# On_Off_Switches.net
KiCad netlist of a schematic drawn in Altium Designer
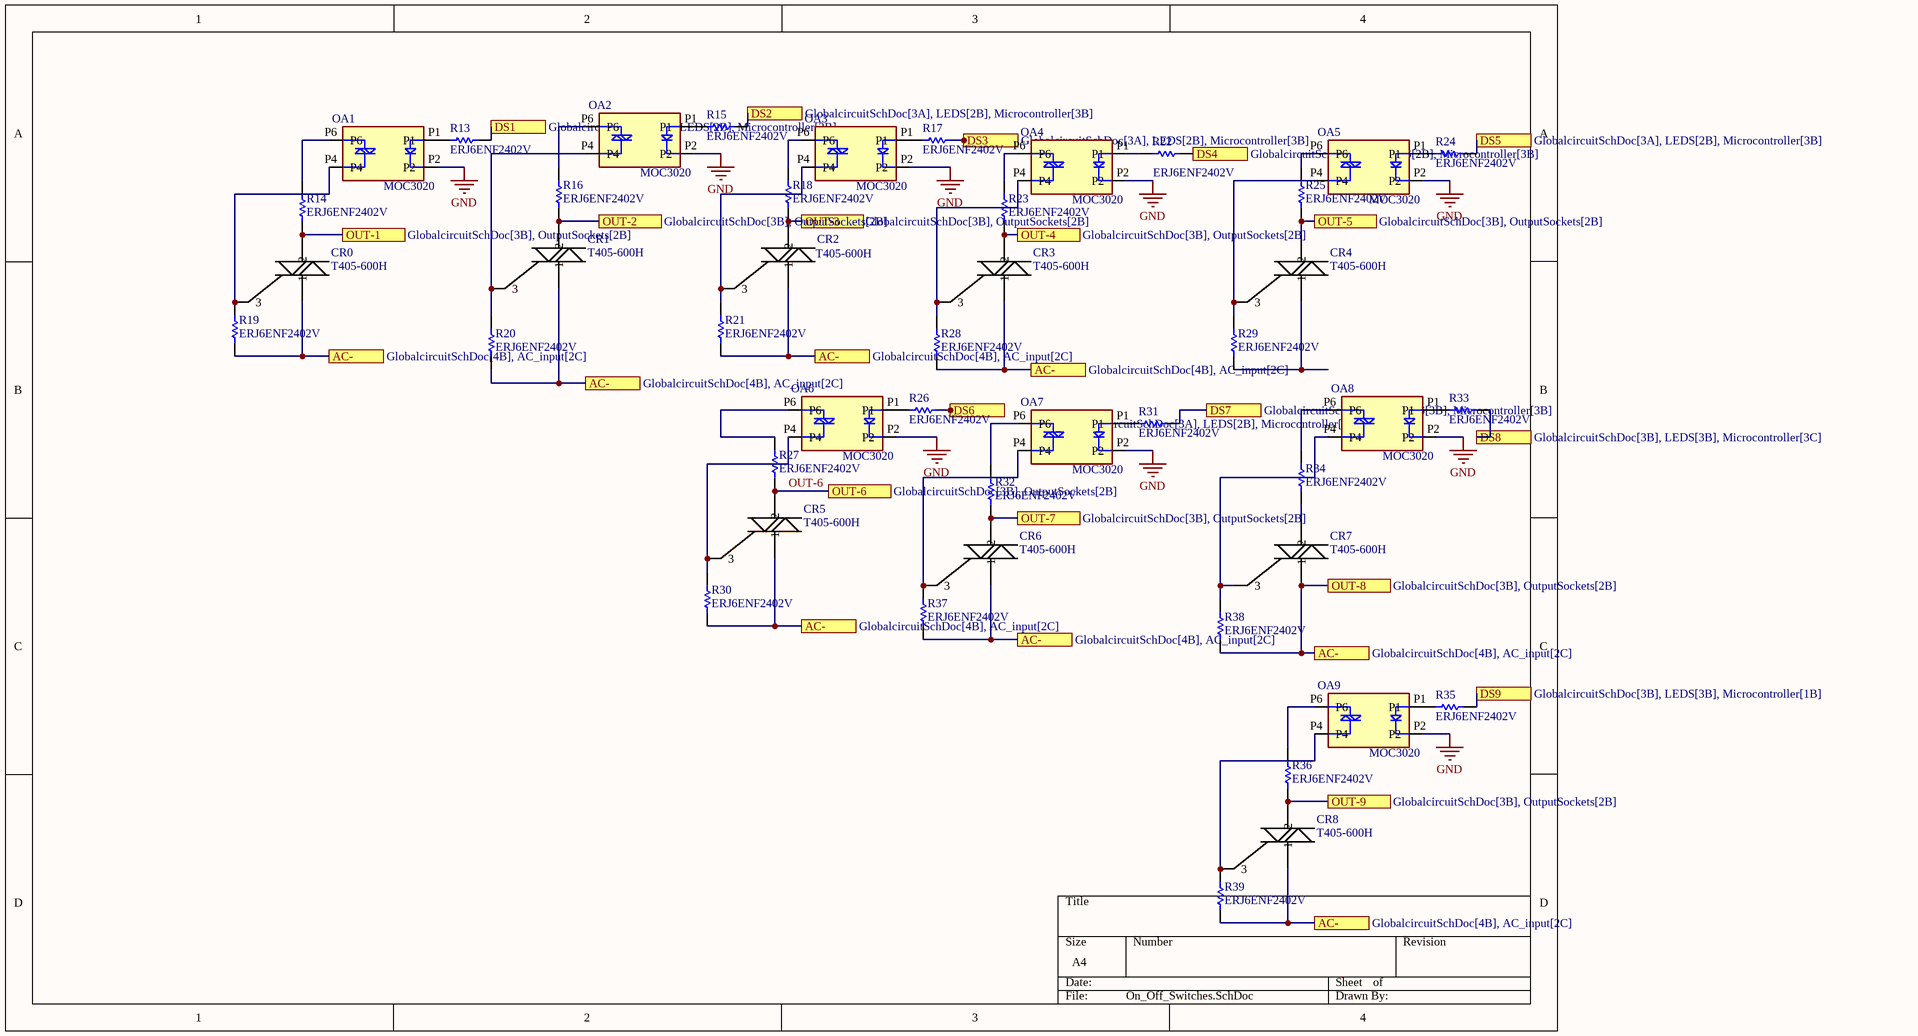
[diagram p0: On_Off_Switches.SchDoc]

(export (version "E")
  (design (tool "Eeschema 10.0.6"))
  (components
    (comp (ref "CR0")
      (value "T405-600H")
      (footprint "IPAK_STM")
      (description "No Description Available")
      (libsource (lib "T405-600H") (part "T405-600H"))
    )
    (comp (ref "CR1")
      (value "T405-600H")
      (footprint "IPAK_STM")
      (description "No Description Available")
      (libsource (lib "T405-600H") (part "T405-600H"))
    )
    (comp (ref "CR2")
      (value "T405-600H")
      (footprint "IPAK_STM")
      (description "No Description Available")
      (libsource (lib "T405-600H") (part "T405-600H"))
    )
    (comp (ref "CR3")
      (value "T405-600H")
      (footprint "IPAK_STM")
      (description "No Description Available")
      (libsource (lib "T405-600H") (part "T405-600H"))
    )
    (comp (ref "CR4")
      (value "T405-600H")
      (footprint "IPAK_STM")
      (description "No Description Available")
      (libsource (lib "T405-600H") (part "T405-600H"))
    )
    (comp (ref "CR5")
      (value "T405-600H")
      (footprint "IPAK_STM")
      (description "No Description Available")
      (libsource (lib "T405-600H") (part "T405-600H"))
    )
    (comp (ref "CR6")
      (value "T405-600H")
      (footprint "IPAK_STM")
      (description "No Description Available")
      (libsource (lib "T405-600H") (part "T405-600H"))
    )
    (comp (ref "CR7")
      (value "T405-600H")
      (footprint "IPAK_STM")
      (description "No Description Available")
      (libsource (lib "T405-600H") (part "T405-600H"))
    )
    (comp (ref "CR8")
      (value "T405-600H")
      (footprint "IPAK_STM")
      (description "No Description Available")
      (libsource (lib "T405-600H") (part "T405-600H"))
    )
    (comp (ref "OA1")
      (value "MOC3020S")
      (footprint "MOC3020S")
      (description "Optoisolator Triac Output 5000Vrms 1 Channel 6-SMD")
      (fields (field (name "MF") "Lite-On Inc."))
      (libsource (lib "MOC3020S") (part "MOC3020S"))
    )
    (comp (ref "OA2")
      (value "MOC3020S")
      (footprint "MOC3020S")
      (description "Optoisolator Triac Output 5000Vrms 1 Channel 6-SMD")
      (fields (field (name "MF") "Lite-On Inc."))
      (libsource (lib "MOC3020S") (part "MOC3020S"))
    )
    (comp (ref "OA3")
      (value "MOC3020S")
      (footprint "MOC3020S")
      (description "Optoisolator Triac Output 5000Vrms 1 Channel 6-SMD")
      (fields (field (name "MF") "Lite-On Inc."))
      (libsource (lib "MOC3020S") (part "MOC3020S"))
    )
    (comp (ref "OA4")
      (value "MOC3020S")
      (footprint "MOC3020S")
      (description "Optoisolator Triac Output 5000Vrms 1 Channel 6-SMD")
      (fields (field (name "MF") "Lite-On Inc."))
      (libsource (lib "MOC3020S") (part "MOC3020S"))
    )
    (comp (ref "OA5")
      (value "MOC3020S")
      (footprint "MOC3020S")
      (description "Optoisolator Triac Output 5000Vrms 1 Channel 6-SMD")
      (fields (field (name "MF") "Lite-On Inc."))
      (libsource (lib "MOC3020S") (part "MOC3020S"))
    )
    (comp (ref "OA6")
      (value "MOC3020S")
      (footprint "MOC3020S")
      (description "Optoisolator Triac Output 5000Vrms 1 Channel 6-SMD")
      (fields (field (name "MF") "Lite-On Inc."))
      (libsource (lib "MOC3020S") (part "MOC3020S"))
    )
    (comp (ref "OA7")
      (value "MOC3020S")
      (footprint "MOC3020S")
      (description "Optoisolator Triac Output 5000Vrms 1 Channel 6-SMD")
      (fields (field (name "MF") "Lite-On Inc."))
      (libsource (lib "MOC3020S") (part "MOC3020S"))
    )
    (comp (ref "OA8")
      (value "MOC3020S")
      (footprint "MOC3020S")
      (description "Optoisolator Triac Output 5000Vrms 1 Channel 6-SMD")
      (fields (field (name "MF") "Lite-On Inc."))
      (libsource (lib "MOC3020S") (part "MOC3020S"))
    )
    (comp (ref "OA9")
      (value "MOC3020S")
      (footprint "MOC3020S")
      (description "Optoisolator Triac Output 5000Vrms 1 Channel 6-SMD")
      (fields (field (name "MF") "Lite-On Inc."))
      (libsource (lib "MOC3020S") (part "MOC3020S"))
    )
    (comp (ref "R13")
      (value "ERJ6ENF2402V")
      (footprint "RESC2013X70X40ML20T20")
      (fields (field (name "MANUFACTURER") "Panasonic"))
      (libsource (lib "Altium Content Vault") (part "RES"))
    )
    (comp (ref "R14")
      (value "ERJ6ENF2402V")
      (footprint "RESC2013X70X40ML20T20")
      (fields (field (name "MANUFACTURER") "Panasonic"))
      (libsource (lib "Altium Content Vault") (part "RES"))
    )
    (comp (ref "R15")
      (value "ERJ6ENF2402V")
      (footprint "RESC2013X70X40ML20T20")
      (fields (field (name "MANUFACTURER") "Panasonic"))
      (libsource (lib "Altium Content Vault") (part "RES"))
    )
    (comp (ref "R16")
      (value "ERJ6ENF2402V")
      (footprint "RESC2013X70X40ML20T20")
      (fields (field (name "MANUFACTURER") "Panasonic"))
      (libsource (lib "Altium Content Vault") (part "RES"))
    )
    (comp (ref "R17")
      (value "ERJ6ENF2402V")
      (footprint "RESC2013X70X40ML20T20")
      (fields (field (name "MANUFACTURER") "Panasonic"))
      (libsource (lib "Altium Content Vault") (part "RES"))
    )
    (comp (ref "R18")
      (value "ERJ6ENF2402V")
      (footprint "RESC2013X70X40ML20T20")
      (fields (field (name "MANUFACTURER") "Panasonic"))
      (libsource (lib "Altium Content Vault") (part "RES"))
    )
    (comp (ref "R19")
      (value "ERJ6ENF2402V")
      (footprint "RESC2013X70X40ML20T20")
      (fields (field (name "MANUFACTURER") "Panasonic"))
      (libsource (lib "Altium Content Vault") (part "RES"))
    )
    (comp (ref "R20")
      (value "ERJ6ENF2402V")
      (footprint "RESC2013X70X40ML20T20")
      (fields (field (name "MANUFACTURER") "Panasonic"))
      (libsource (lib "Altium Content Vault") (part "RES"))
    )
    (comp (ref "R21")
      (value "ERJ6ENF2402V")
      (footprint "RESC2013X70X40ML20T20")
      (fields (field (name "MANUFACTURER") "Panasonic"))
      (libsource (lib "Altium Content Vault") (part "RES"))
    )
    (comp (ref "R22")
      (value "ERJ6ENF2402V")
      (footprint "RESC2013X70X40ML20T20")
      (fields (field (name "MANUFACTURER") "Panasonic"))
      (libsource (lib "Altium Content Vault") (part "RES"))
    )
    (comp (ref "R23")
      (value "ERJ6ENF2402V")
      (footprint "RESC2013X70X40ML20T20")
      (fields (field (name "MANUFACTURER") "Panasonic"))
      (libsource (lib "Altium Content Vault") (part "RES"))
    )
    (comp (ref "R24")
      (value "ERJ6ENF2402V")
      (footprint "RESC2013X70X40ML20T20")
      (fields (field (name "MANUFACTURER") "Panasonic"))
      (libsource (lib "Altium Content Vault") (part "RES"))
    )
    (comp (ref "R25")
      (value "ERJ6ENF2402V")
      (footprint "RESC2013X70X40ML20T20")
      (fields (field (name "MANUFACTURER") "Panasonic"))
      (libsource (lib "Altium Content Vault") (part "RES"))
    )
    (comp (ref "R26")
      (value "ERJ6ENF2402V")
      (footprint "RESC2013X70X40ML20T20")
      (fields (field (name "MANUFACTURER") "Panasonic"))
      (libsource (lib "Altium Content Vault") (part "RES"))
    )
    (comp (ref "R27")
      (value "ERJ6ENF2402V")
      (footprint "RESC2013X70X40ML20T20")
      (fields (field (name "MANUFACTURER") "Panasonic"))
      (libsource (lib "Altium Content Vault") (part "RES"))
    )
    (comp (ref "R28")
      (value "ERJ6ENF2402V")
      (footprint "RESC2013X70X40ML20T20")
      (fields (field (name "MANUFACTURER") "Panasonic"))
      (libsource (lib "Altium Content Vault") (part "RES"))
    )
    (comp (ref "R29")
      (value "ERJ6ENF2402V")
      (footprint "RESC2013X70X40ML20T20")
      (fields (field (name "MANUFACTURER") "Panasonic"))
      (libsource (lib "Altium Content Vault") (part "RES"))
    )
    (comp (ref "R30")
      (value "ERJ6ENF2402V")
      (footprint "RESC2013X70X40ML20T20")
      (fields (field (name "MANUFACTURER") "Panasonic"))
      (libsource (lib "Altium Content Vault") (part "RES"))
    )
    (comp (ref "R31")
      (value "ERJ6ENF2402V")
      (footprint "RESC2013X70X40ML20T20")
      (fields (field (name "MANUFACTURER") "Panasonic"))
      (libsource (lib "Altium Content Vault") (part "RES"))
    )
    (comp (ref "R32")
      (value "ERJ6ENF2402V")
      (footprint "RESC2013X70X40ML20T20")
      (fields (field (name "MANUFACTURER") "Panasonic"))
      (libsource (lib "Altium Content Vault") (part "RES"))
    )
    (comp (ref "R33")
      (value "ERJ6ENF2402V")
      (footprint "RESC2013X70X40ML20T20")
      (fields (field (name "MANUFACTURER") "Panasonic"))
      (libsource (lib "Altium Content Vault") (part "RES"))
    )
    (comp (ref "R34")
      (value "ERJ6ENF2402V")
      (footprint "RESC2013X70X40ML20T20")
      (fields (field (name "MANUFACTURER") "Panasonic"))
      (libsource (lib "Altium Content Vault") (part "RES"))
    )
    (comp (ref "R35")
      (value "ERJ6ENF2402V")
      (footprint "RESC2013X70X40ML20T20")
      (fields (field (name "MANUFACTURER") "Panasonic"))
      (libsource (lib "Altium Content Vault") (part "RES"))
    )
    (comp (ref "R36")
      (value "ERJ6ENF2402V")
      (footprint "RESC2013X70X40ML20T20")
      (fields (field (name "MANUFACTURER") "Panasonic"))
      (libsource (lib "Altium Content Vault") (part "RES"))
    )
    (comp (ref "R37")
      (value "ERJ6ENF2402V")
      (footprint "RESC2013X70X40ML20T20")
      (fields (field (name "MANUFACTURER") "Panasonic"))
      (libsource (lib "Altium Content Vault") (part "RES"))
    )
    (comp (ref "R38")
      (value "ERJ6ENF2402V")
      (footprint "RESC2013X70X40ML20T20")
      (fields (field (name "MANUFACTURER") "Panasonic"))
      (libsource (lib "Altium Content Vault") (part "RES"))
    )
    (comp (ref "R39")
      (value "ERJ6ENF2402V")
      (footprint "RESC2013X70X40ML20T20")
      (fields (field (name "MANUFACTURER") "Panasonic"))
      (libsource (lib "Altium Content Vault") (part "RES"))
    )
  )
  (nets
    (net (code "1") (name "/AC-") (class "Default")
      (node (ref "CR0") (pin "1") (pinfunction "1_1") (pintype "passive"))
      (node (ref "CR1") (pin "1") (pinfunction "1_1") (pintype "passive"))
      (node (ref "CR2") (pin "1") (pinfunction "1_1") (pintype "passive"))
      (node (ref "CR3") (pin "1") (pinfunction "1_1") (pintype "passive"))
      (node (ref "CR5") (pin "1") (pinfunction "1_1") (pintype "passive"))
      (node (ref "CR6") (pin "1") (pinfunction "1_1") (pintype "passive"))
      (node (ref "CR7") (pin "1") (pinfunction "1_1") (pintype "passive"))
      (node (ref "CR8") (pin "1") (pinfunction "1_1") (pintype "passive"))
      (node (ref "R19") (pin "1") (pinfunction "1_1") (pintype "passive"))
      (node (ref "R20") (pin "1") (pinfunction "1_1") (pintype "passive"))
      (node (ref "R21") (pin "1") (pinfunction "1_1") (pintype "passive"))
      (node (ref "R28") (pin "1") (pinfunction "1_1") (pintype "passive"))
      (node (ref "R30") (pin "1") (pinfunction "1_1") (pintype "passive"))
      (node (ref "R37") (pin "1") (pinfunction "1_1") (pintype "passive"))
      (node (ref "R38") (pin "1") (pinfunction "1_1") (pintype "passive"))
      (node (ref "R39") (pin "1") (pinfunction "1_1") (pintype "passive"))
    )
    (net (code "2") (name "/DS1") (class "Default")
      (node (ref "R13") (pin "1") (pinfunction "1_1") (pintype "passive"))
    )
    (net (code "3") (name "/DS2") (class "Default")
      (node (ref "R15") (pin "1") (pinfunction "1_1") (pintype "passive"))
    )
    (net (code "4") (name "/DS3") (class "Default")
      (node (ref "R17") (pin "1") (pinfunction "1_1") (pintype "passive"))
    )
    (net (code "5") (name "/DS4") (class "Default")
      (node (ref "R22") (pin "1") (pinfunction "1_1") (pintype "passive"))
    )
    (net (code "6") (name "/DS5") (class "Default")
      (node (ref "R24") (pin "1") (pinfunction "1_1") (pintype "passive"))
    )
    (net (code "7") (name "/DS6") (class "Default")
      (node (ref "R26") (pin "1") (pinfunction "1_1") (pintype "passive"))
    )
    (net (code "8") (name "/DS7") (class "Default")
      (node (ref "R31") (pin "1") (pinfunction "1_1") (pintype "passive"))
    )
    (net (code "9") (name "/DS8") (class "Default")
      (node (ref "R33") (pin "1") (pinfunction "1_1") (pintype "passive"))
    )
    (net (code "10") (name "/DS9") (class "Default")
      (node (ref "R35") (pin "1") (pinfunction "1_1") (pintype "passive"))
    )
    (net (code "11") (name "/OUT-1") (class "Default")
      (node (ref "CR0") (pin "2") (pinfunction "2_2") (pintype "passive"))
      (node (ref "R14") (pin "1") (pinfunction "1_1") (pintype "passive"))
    )
    (net (code "12") (name "/OUT-2") (class "Default")
      (node (ref "CR1") (pin "2") (pinfunction "2_2") (pintype "passive"))
      (node (ref "R16") (pin "1") (pinfunction "1_1") (pintype "passive"))
    )
    (net (code "13") (name "/OUT-3") (class "Default")
      (node (ref "CR2") (pin "2") (pinfunction "2_2") (pintype "passive"))
      (node (ref "R18") (pin "1") (pinfunction "1_1") (pintype "passive"))
    )
    (net (code "14") (name "/OUT-4") (class "Default")
      (node (ref "CR3") (pin "2") (pinfunction "2_2") (pintype "passive"))
      (node (ref "R23") (pin "1") (pinfunction "1_1") (pintype "passive"))
    )
    (net (code "15") (name "/OUT-5") (class "Default")
      (node (ref "CR4") (pin "2") (pinfunction "2_2") (pintype "passive"))
      (node (ref "R25") (pin "1") (pinfunction "1_1") (pintype "passive"))
    )
    (net (code "16") (name "/OUT-6") (class "Default")
      (node (ref "CR5") (pin "2") (pinfunction "2_2") (pintype "passive"))
      (node (ref "R27") (pin "1") (pinfunction "1_1") (pintype "passive"))
    )
    (net (code "17") (name "/OUT-7") (class "Default")
      (node (ref "CR6") (pin "2") (pinfunction "2_2") (pintype "passive"))
      (node (ref "R32") (pin "1") (pinfunction "1_1") (pintype "passive"))
    )
    (net (code "18") (name "/OUT-9") (class "Default")
      (node (ref "CR8") (pin "2") (pinfunction "2_2") (pintype "passive"))
      (node (ref "R36") (pin "1") (pinfunction "1_1") (pintype "passive"))
    )
    (net (code "19") (name "GND") (class "Default")
      (node (ref "OA1") (pin "P2") (pinfunction "P2_P2") (pintype "bidirectional"))
      (node (ref "OA2") (pin "P2") (pinfunction "P2_P2") (pintype "bidirectional"))
      (node (ref "OA3") (pin "P2") (pinfunction "P2_P2") (pintype "bidirectional"))
      (node (ref "OA4") (pin "P2") (pinfunction "P2_P2") (pintype "bidirectional"))
      (node (ref "OA5") (pin "P2") (pinfunction "P2_P2") (pintype "bidirectional"))
      (node (ref "OA6") (pin "P2") (pinfunction "P2_P2") (pintype "bidirectional"))
      (node (ref "OA7") (pin "P2") (pinfunction "P2_P2") (pintype "bidirectional"))
      (node (ref "OA8") (pin "P2") (pinfunction "P2_P2") (pintype "bidirectional"))
      (node (ref "OA9") (pin "P2") (pinfunction "P2_P2") (pintype "bidirectional"))
    )
    (net (code "20") (name "Net-(CR0-Pad3)") (class "Default")
      (node (ref "CR0") (pin "3") (pinfunction "3_3") (pintype "passive"))
      (node (ref "OA1") (pin "P4") (pinfunction "P4_P4") (pintype "bidirectional"))
      (node (ref "R19") (pin "2") (pinfunction "2_2") (pintype "passive"))
    )
    (net (code "21") (name "Net-(CR1-Pad3)") (class "Default")
      (node (ref "CR1") (pin "3") (pinfunction "3_3") (pintype "passive"))
      (node (ref "OA2") (pin "P4") (pinfunction "P4_P4") (pintype "bidirectional"))
      (node (ref "R20") (pin "2") (pinfunction "2_2") (pintype "passive"))
    )
    (net (code "22") (name "Net-(CR2-Pad3)") (class "Default")
      (node (ref "CR2") (pin "3") (pinfunction "3_3") (pintype "passive"))
      (node (ref "OA3") (pin "P4") (pinfunction "P4_P4") (pintype "bidirectional"))
      (node (ref "R21") (pin "2") (pinfunction "2_2") (pintype "passive"))
    )
    (net (code "23") (name "Net-(CR3-Pad3)") (class "Default")
      (node (ref "CR3") (pin "3") (pinfunction "3_3") (pintype "passive"))
      (node (ref "OA4") (pin "P4") (pinfunction "P4_P4") (pintype "bidirectional"))
      (node (ref "R28") (pin "2") (pinfunction "2_2") (pintype "passive"))
    )
    (net (code "24") (name "Net-(CR4-Pad1)") (class "Default")
      (node (ref "CR4") (pin "1") (pinfunction "1_1") (pintype "passive"))
      (node (ref "R29") (pin "1") (pinfunction "1_1") (pintype "passive"))
    )
    (net (code "25") (name "Net-(CR4-Pad3)") (class "Default")
      (node (ref "CR4") (pin "3") (pinfunction "3_3") (pintype "passive"))
      (node (ref "OA5") (pin "P4") (pinfunction "P4_P4") (pintype "bidirectional"))
      (node (ref "R29") (pin "2") (pinfunction "2_2") (pintype "passive"))
    )
    (net (code "26") (name "Net-(CR5-Pad3)") (class "Default")
      (node (ref "CR5") (pin "3") (pinfunction "3_3") (pintype "passive"))
      (node (ref "OA6") (pin "P4") (pinfunction "P4_P4") (pintype "bidirectional"))
      (node (ref "R30") (pin "2") (pinfunction "2_2") (pintype "passive"))
    )
    (net (code "27") (name "Net-(CR6-Pad3)") (class "Default")
      (node (ref "CR6") (pin "3") (pinfunction "3_3") (pintype "passive"))
      (node (ref "OA7") (pin "P4") (pinfunction "P4_P4") (pintype "bidirectional"))
      (node (ref "R37") (pin "2") (pinfunction "2_2") (pintype "passive"))
    )
    (net (code "28") (name "Net-(CR7-Pad2)") (class "Default")
      (node (ref "CR7") (pin "2") (pinfunction "2_2") (pintype "passive"))
      (node (ref "R34") (pin "1") (pinfunction "1_1") (pintype "passive"))
    )
    (net (code "29") (name "Net-(CR7-Pad3)") (class "Default")
      (node (ref "CR7") (pin "3") (pinfunction "3_3") (pintype "passive"))
      (node (ref "OA8") (pin "P4") (pinfunction "P4_P4") (pintype "bidirectional"))
      (node (ref "R38") (pin "2") (pinfunction "2_2") (pintype "passive"))
    )
    (net (code "30") (name "Net-(CR8-Pad3)") (class "Default")
      (node (ref "CR8") (pin "3") (pinfunction "3_3") (pintype "passive"))
      (node (ref "OA9") (pin "P4") (pinfunction "P4_P4") (pintype "bidirectional"))
      (node (ref "R39") (pin "2") (pinfunction "2_2") (pintype "passive"))
    )
    (net (code "31") (name "Net-(OA1-PadP1)") (class "Default")
      (node (ref "OA1") (pin "P1") (pinfunction "P1_P1") (pintype "bidirectional"))
      (node (ref "R13") (pin "2") (pinfunction "2_2") (pintype "passive"))
    )
    (net (code "32") (name "Net-(OA1-PadP6)") (class "Default")
      (node (ref "OA1") (pin "P6") (pinfunction "P6_P6") (pintype "bidirectional"))
      (node (ref "R14") (pin "2") (pinfunction "2_2") (pintype "passive"))
    )
    (net (code "33") (name "Net-(OA2-PadP1)") (class "Default")
      (node (ref "OA2") (pin "P1") (pinfunction "P1_P1") (pintype "bidirectional"))
      (node (ref "R15") (pin "2") (pinfunction "2_2") (pintype "passive"))
    )
    (net (code "34") (name "Net-(OA2-PadP6)") (class "Default")
      (node (ref "OA2") (pin "P6") (pinfunction "P6_P6") (pintype "bidirectional"))
      (node (ref "R16") (pin "2") (pinfunction "2_2") (pintype "passive"))
    )
    (net (code "35") (name "Net-(OA3-PadP1)") (class "Default")
      (node (ref "OA3") (pin "P1") (pinfunction "P1_P1") (pintype "bidirectional"))
      (node (ref "R17") (pin "2") (pinfunction "2_2") (pintype "passive"))
    )
    (net (code "36") (name "Net-(OA3-PadP6)") (class "Default")
      (node (ref "OA3") (pin "P6") (pinfunction "P6_P6") (pintype "bidirectional"))
      (node (ref "R18") (pin "2") (pinfunction "2_2") (pintype "passive"))
    )
    (net (code "37") (name "Net-(OA4-PadP1)") (class "Default")
      (node (ref "OA4") (pin "P1") (pinfunction "P1_P1") (pintype "bidirectional"))
      (node (ref "R22") (pin "2") (pinfunction "2_2") (pintype "passive"))
    )
    (net (code "38") (name "Net-(OA4-PadP6)") (class "Default")
      (node (ref "OA4") (pin "P6") (pinfunction "P6_P6") (pintype "bidirectional"))
      (node (ref "R23") (pin "2") (pinfunction "2_2") (pintype "passive"))
    )
    (net (code "39") (name "Net-(OA5-PadP1)") (class "Default")
      (node (ref "OA5") (pin "P1") (pinfunction "P1_P1") (pintype "bidirectional"))
      (node (ref "R24") (pin "2") (pinfunction "2_2") (pintype "passive"))
    )
    (net (code "40") (name "Net-(OA5-PadP6)") (class "Default")
      (node (ref "OA5") (pin "P6") (pinfunction "P6_P6") (pintype "bidirectional"))
      (node (ref "R25") (pin "2") (pinfunction "2_2") (pintype "passive"))
    )
    (net (code "41") (name "Net-(OA6-PadP1)") (class "Default")
      (node (ref "OA6") (pin "P1") (pinfunction "P1_P1") (pintype "bidirectional"))
      (node (ref "R26") (pin "2") (pinfunction "2_2") (pintype "passive"))
    )
    (net (code "42") (name "Net-(OA6-PadP6)") (class "Default")
      (node (ref "OA6") (pin "P6") (pinfunction "P6_P6") (pintype "bidirectional"))
      (node (ref "R27") (pin "2") (pinfunction "2_2") (pintype "passive"))
    )
    (net (code "43") (name "Net-(OA7-PadP1)") (class "Default")
      (node (ref "OA7") (pin "P1") (pinfunction "P1_P1") (pintype "bidirectional"))
      (node (ref "R31") (pin "2") (pinfunction "2_2") (pintype "passive"))
    )
    (net (code "44") (name "Net-(OA7-PadP6)") (class "Default")
      (node (ref "OA7") (pin "P6") (pinfunction "P6_P6") (pintype "bidirectional"))
      (node (ref "R32") (pin "2") (pinfunction "2_2") (pintype "passive"))
    )
    (net (code "45") (name "Net-(OA8-PadP1)") (class "Default")
      (node (ref "OA8") (pin "P1") (pinfunction "P1_P1") (pintype "bidirectional"))
      (node (ref "R33") (pin "2") (pinfunction "2_2") (pintype "passive"))
    )
    (net (code "46") (name "Net-(OA8-PadP6)") (class "Default")
      (node (ref "OA8") (pin "P6") (pinfunction "P6_P6") (pintype "bidirectional"))
      (node (ref "R34") (pin "2") (pinfunction "2_2") (pintype "passive"))
    )
    (net (code "47") (name "Net-(OA9-PadP1)") (class "Default")
      (node (ref "OA9") (pin "P1") (pinfunction "P1_P1") (pintype "bidirectional"))
      (node (ref "R35") (pin "2") (pinfunction "2_2") (pintype "passive"))
    )
    (net (code "48") (name "Net-(OA9-PadP6)") (class "Default")
      (node (ref "OA9") (pin "P6") (pinfunction "P6_P6") (pintype "bidirectional"))
      (node (ref "R36") (pin "2") (pinfunction "2_2") (pintype "passive"))
    )
  )
)
